# vstupyPCF8574.net
KiCad netlist of a schematic drawn in EAGLE
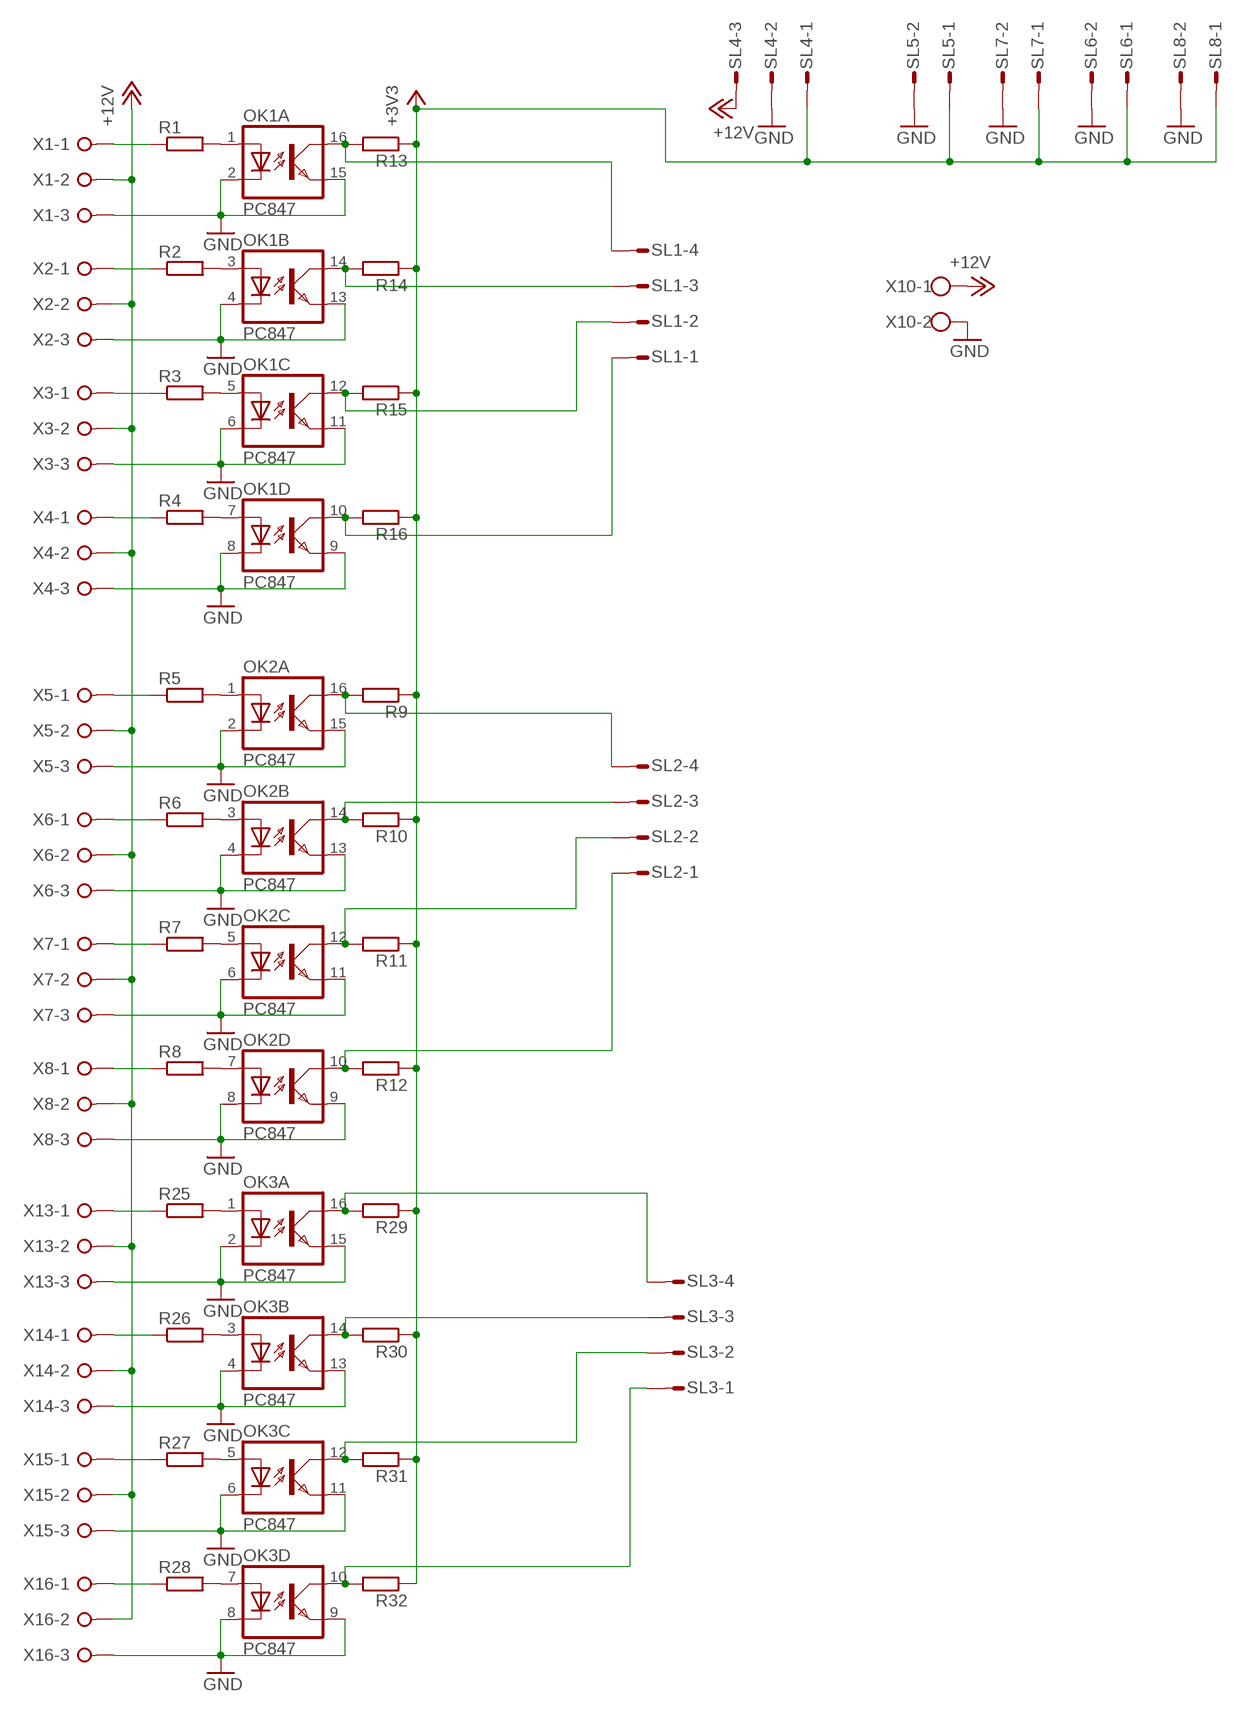
[diagram p0: schematic, sheet 1]

(export (version "E")
  (design (tool "Eeschema 10.0.6"))
  (components
    (comp (ref "OK1")
      (value "PC847")
      (footprint "eagle-import:DIL16")
      (libsource (lib "eagle-import") (part "PC847"))
    )
    (comp (ref "OK2")
      (value "PC847")
      (footprint "eagle-import:DIL16")
      (libsource (lib "eagle-import") (part "PC847"))
    )
    (comp (ref "OK3")
      (value "PC847")
      (footprint "eagle-import:DIL16")
      (libsource (lib "eagle-import") (part "PC847"))
    )
    (comp (ref "R1")
      (value "R-EU_0204/5")
      (footprint "eagle-import:0204_5")
      (libsource (lib "eagle-import") (part "R-EU_0204/5"))
    )
    (comp (ref "R2")
      (value "R-EU_0204/5")
      (footprint "eagle-import:0204_5")
      (libsource (lib "eagle-import") (part "R-EU_0204/5"))
    )
    (comp (ref "R3")
      (value "R-EU_0204/5")
      (footprint "eagle-import:0204_5")
      (libsource (lib "eagle-import") (part "R-EU_0204/5"))
    )
    (comp (ref "R4")
      (value "R-EU_0204/5")
      (footprint "eagle-import:0204_5")
      (libsource (lib "eagle-import") (part "R-EU_0204/5"))
    )
    (comp (ref "R5")
      (value "R-EU_0204/5")
      (footprint "eagle-import:0204_5")
      (libsource (lib "eagle-import") (part "R-EU_0204/5"))
    )
    (comp (ref "R6")
      (value "R-EU_0204/5")
      (footprint "eagle-import:0204_5")
      (libsource (lib "eagle-import") (part "R-EU_0204/5"))
    )
    (comp (ref "R7")
      (value "R-EU_0204/5")
      (footprint "eagle-import:0204_5")
      (libsource (lib "eagle-import") (part "R-EU_0204/5"))
    )
    (comp (ref "R8")
      (value "R-EU_0204/5")
      (footprint "eagle-import:0204_5")
      (libsource (lib "eagle-import") (part "R-EU_0204/5"))
    )
    (comp (ref "R9")
      (value "R-EU_0204/5")
      (footprint "eagle-import:0204_5")
      (libsource (lib "eagle-import") (part "R-EU_0204/5"))
    )
    (comp (ref "R10")
      (value "R-EU_0204/5")
      (footprint "eagle-import:0204_5")
      (libsource (lib "eagle-import") (part "R-EU_0204/5"))
    )
    (comp (ref "R11")
      (value "R-EU_0204/5")
      (footprint "eagle-import:0204_5")
      (libsource (lib "eagle-import") (part "R-EU_0204/5"))
    )
    (comp (ref "R12")
      (value "R-EU_0204/5")
      (footprint "eagle-import:0204_5")
      (libsource (lib "eagle-import") (part "R-EU_0204/5"))
    )
    (comp (ref "R13")
      (value "R-EU_0204/5")
      (footprint "eagle-import:0204_5")
      (libsource (lib "eagle-import") (part "R-EU_0204/5"))
    )
    (comp (ref "R14")
      (value "R-EU_0204/5")
      (footprint "eagle-import:0204_5")
      (libsource (lib "eagle-import") (part "R-EU_0204/5"))
    )
    (comp (ref "R15")
      (value "R-EU_0204/5")
      (footprint "eagle-import:0204_5")
      (libsource (lib "eagle-import") (part "R-EU_0204/5"))
    )
    (comp (ref "R16")
      (value "R-EU_0204/5")
      (footprint "eagle-import:0204_5")
      (libsource (lib "eagle-import") (part "R-EU_0204/5"))
    )
    (comp (ref "R25")
      (value "R-EU_0204/5")
      (footprint "eagle-import:0204_5")
      (libsource (lib "eagle-import") (part "R-EU_0204/5"))
    )
    (comp (ref "R26")
      (value "R-EU_0204/5")
      (footprint "eagle-import:0204_5")
      (libsource (lib "eagle-import") (part "R-EU_0204/5"))
    )
    (comp (ref "R27")
      (value "R-EU_0204/5")
      (footprint "eagle-import:0204_5")
      (libsource (lib "eagle-import") (part "R-EU_0204/5"))
    )
    (comp (ref "R28")
      (value "R-EU_0204/5")
      (footprint "eagle-import:0204_5")
      (libsource (lib "eagle-import") (part "R-EU_0204/5"))
    )
    (comp (ref "R29")
      (value "R-EU_0204/5")
      (footprint "eagle-import:0204_5")
      (libsource (lib "eagle-import") (part "R-EU_0204/5"))
    )
    (comp (ref "R30")
      (value "R-EU_0204/5")
      (footprint "eagle-import:0204_5")
      (libsource (lib "eagle-import") (part "R-EU_0204/5"))
    )
    (comp (ref "R31")
      (value "R-EU_0204/5")
      (footprint "eagle-import:0204_5")
      (libsource (lib "eagle-import") (part "R-EU_0204/5"))
    )
    (comp (ref "R32")
      (value "R-EU_0204/5")
      (footprint "eagle-import:0204_5")
      (libsource (lib "eagle-import") (part "R-EU_0204/5"))
    )
    (comp (ref "SL1")
      (value "M04S")
      (footprint "eagle-import:04P")
      (libsource (lib "eagle-import") (part "M04S"))
    )
    (comp (ref "SL2")
      (value "M04S")
      (footprint "eagle-import:04P")
      (libsource (lib "eagle-import") (part "M04S"))
    )
    (comp (ref "SL3")
      (value "M04S")
      (footprint "eagle-import:04P")
      (libsource (lib "eagle-import") (part "M04S"))
    )
    (comp (ref "SL4")
      (value "M03S")
      (footprint "eagle-import:03P")
      (libsource (lib "eagle-import") (part "M03S"))
    )
    (comp (ref "SL5")
      (value "M02S")
      (footprint "eagle-import:02P")
      (libsource (lib "eagle-import") (part "M02S"))
    )
    (comp (ref "SL6")
      (value "M02S")
      (footprint "eagle-import:02P")
      (libsource (lib "eagle-import") (part "M02S"))
    )
    (comp (ref "SL7")
      (value "M02S")
      (footprint "eagle-import:02P")
      (libsource (lib "eagle-import") (part "M02S"))
    )
    (comp (ref "SL8")
      (value "M02S")
      (footprint "eagle-import:02P")
      (libsource (lib "eagle-import") (part "M02S"))
    )
    (comp (ref "X1")
      (value "W237-3E")
      (footprint "eagle-import:W237-3E")
      (libsource (lib "eagle-import") (part "W237-3E"))
    )
    (comp (ref "X2")
      (value "W237-3E")
      (footprint "eagle-import:W237-3E")
      (libsource (lib "eagle-import") (part "W237-3E"))
    )
    (comp (ref "X3")
      (value "W237-3E")
      (footprint "eagle-import:W237-3E")
      (libsource (lib "eagle-import") (part "W237-3E"))
    )
    (comp (ref "X4")
      (value "W237-3E")
      (footprint "eagle-import:W237-3E")
      (libsource (lib "eagle-import") (part "W237-3E"))
    )
    (comp (ref "X5")
      (value "W237-3E")
      (footprint "eagle-import:W237-3E")
      (libsource (lib "eagle-import") (part "W237-3E"))
    )
    (comp (ref "X6")
      (value "W237-3E")
      (footprint "eagle-import:W237-3E")
      (libsource (lib "eagle-import") (part "W237-3E"))
    )
    (comp (ref "X7")
      (value "W237-3E")
      (footprint "eagle-import:W237-3E")
      (libsource (lib "eagle-import") (part "W237-3E"))
    )
    (comp (ref "X8")
      (value "W237-3E")
      (footprint "eagle-import:W237-3E")
      (libsource (lib "eagle-import") (part "W237-3E"))
    )
    (comp (ref "X10")
      (value "W237-102")
      (footprint "eagle-import:W237-102")
      (fields (field (name "MPN") "237-102"))
      (libsource (lib "eagle-import") (part "W237-102"))
    )
    (comp (ref "X13")
      (value "W237-3E")
      (footprint "eagle-import:W237-3E")
      (libsource (lib "eagle-import") (part "W237-3E"))
    )
    (comp (ref "X14")
      (value "W237-3E")
      (footprint "eagle-import:W237-3E")
      (libsource (lib "eagle-import") (part "W237-3E"))
    )
    (comp (ref "X15")
      (value "W237-3E")
      (footprint "eagle-import:W237-3E")
      (libsource (lib "eagle-import") (part "W237-3E"))
    )
    (comp (ref "X16")
      (value "W237-3E")
      (footprint "eagle-import:W237-3E")
      (libsource (lib "eagle-import") (part "W237-3E"))
    )
  )
  (nets
    (net (code "1") (name "+3V3") (class "Default")
      (node (ref "R10") (pin "1") (pinfunction "1_1") (pintype "passive"))
      (node (ref "R11") (pin "1") (pinfunction "1_1") (pintype "passive"))
      (node (ref "R12") (pin "1") (pinfunction "1_1") (pintype "passive"))
      (node (ref "R13") (pin "1") (pinfunction "1_1") (pintype "passive"))
      (node (ref "R14") (pin "1") (pinfunction "1_1") (pintype "passive"))
      (node (ref "R15") (pin "1") (pinfunction "1_1") (pintype "passive"))
      (node (ref "R16") (pin "1") (pinfunction "1_1") (pintype "passive"))
      (node (ref "R29") (pin "1") (pinfunction "1_1") (pintype "passive"))
      (node (ref "R30") (pin "1") (pinfunction "1_1") (pintype "passive"))
      (node (ref "R31") (pin "1") (pinfunction "1_1") (pintype "passive"))
      (node (ref "R32") (pin "1") (pinfunction "1_1") (pintype "passive"))
      (node (ref "R9") (pin "1") (pinfunction "1_1") (pintype "passive"))
      (node (ref "SL4") (pin "1") (pinfunction "S_1") (pintype "passive"))
      (node (ref "SL5") (pin "1") (pinfunction "S_1") (pintype "passive"))
      (node (ref "SL6") (pin "1") (pinfunction "S_1") (pintype "passive"))
      (node (ref "SL7") (pin "1") (pinfunction "S_1") (pintype "passive"))
      (node (ref "SL8") (pin "1") (pinfunction "S_1") (pintype "passive"))
    )
    (net (code "2") (name "+12V") (class "Default")
      (node (ref "SL4") (pin "3") (pinfunction "S_3") (pintype "passive"))
      (node (ref "X1") (pin "2") (pinfunction "KL_2") (pintype "passive"))
      (node (ref "X10") (pin "1") (pinfunction "KL_1") (pintype "passive"))
      (node (ref "X13") (pin "2") (pinfunction "KL_2") (pintype "passive"))
      (node (ref "X14") (pin "2") (pinfunction "KL_2") (pintype "passive"))
      (node (ref "X15") (pin "2") (pinfunction "KL_2") (pintype "passive"))
      (node (ref "X16") (pin "2") (pinfunction "KL_2") (pintype "passive"))
      (node (ref "X2") (pin "2") (pinfunction "KL_2") (pintype "passive"))
      (node (ref "X3") (pin "2") (pinfunction "KL_2") (pintype "passive"))
      (node (ref "X4") (pin "2") (pinfunction "KL_2") (pintype "passive"))
      (node (ref "X5") (pin "2") (pinfunction "KL_2") (pintype "passive"))
      (node (ref "X6") (pin "2") (pinfunction "KL_2") (pintype "passive"))
      (node (ref "X7") (pin "2") (pinfunction "KL_2") (pintype "passive"))
      (node (ref "X8") (pin "2") (pinfunction "KL_2") (pintype "passive"))
    )
    (net (code "3") (name "GND") (class "Default")
      (node (ref "OK1") (pin "11") (pinfunction "EMIT_11") (pintype "passive"))
      (node (ref "OK1") (pin "13") (pinfunction "EMIT_13") (pintype "passive"))
      (node (ref "OK1") (pin "15") (pinfunction "EMIT_15") (pintype "passive"))
      (node (ref "OK1") (pin "2") (pinfunction "C_2") (pintype "passive"))
      (node (ref "OK1") (pin "4") (pinfunction "C_4") (pintype "passive"))
      (node (ref "OK1") (pin "6") (pinfunction "C_6") (pintype "passive"))
      (node (ref "OK1") (pin "8") (pinfunction "C_8") (pintype "passive"))
      (node (ref "OK1") (pin "9") (pinfunction "EMIT_9") (pintype "passive"))
      (node (ref "OK2") (pin "11") (pinfunction "EMIT_11") (pintype "passive"))
      (node (ref "OK2") (pin "13") (pinfunction "EMIT_13") (pintype "passive"))
      (node (ref "OK2") (pin "15") (pinfunction "EMIT_15") (pintype "passive"))
      (node (ref "OK2") (pin "2") (pinfunction "C_2") (pintype "passive"))
      (node (ref "OK2") (pin "4") (pinfunction "C_4") (pintype "passive"))
      (node (ref "OK2") (pin "6") (pinfunction "C_6") (pintype "passive"))
      (node (ref "OK2") (pin "8") (pinfunction "C_8") (pintype "passive"))
      (node (ref "OK2") (pin "9") (pinfunction "EMIT_9") (pintype "passive"))
      (node (ref "OK3") (pin "11") (pinfunction "EMIT_11") (pintype "passive"))
      (node (ref "OK3") (pin "13") (pinfunction "EMIT_13") (pintype "passive"))
      (node (ref "OK3") (pin "15") (pinfunction "EMIT_15") (pintype "passive"))
      (node (ref "OK3") (pin "2") (pinfunction "C_2") (pintype "passive"))
      (node (ref "OK3") (pin "4") (pinfunction "C_4") (pintype "passive"))
      (node (ref "OK3") (pin "6") (pinfunction "C_6") (pintype "passive"))
      (node (ref "OK3") (pin "8") (pinfunction "C_8") (pintype "passive"))
      (node (ref "OK3") (pin "9") (pinfunction "EMIT_9") (pintype "passive"))
      (node (ref "SL4") (pin "2") (pinfunction "S_2") (pintype "passive"))
      (node (ref "SL5") (pin "2") (pinfunction "S_2") (pintype "passive"))
      (node (ref "SL6") (pin "2") (pinfunction "S_2") (pintype "passive"))
      (node (ref "SL7") (pin "2") (pinfunction "S_2") (pintype "passive"))
      (node (ref "SL8") (pin "2") (pinfunction "S_2") (pintype "passive"))
      (node (ref "X1") (pin "3") (pinfunction "KL_3") (pintype "passive"))
      (node (ref "X10") (pin "2") (pinfunction "KL_2") (pintype "passive"))
      (node (ref "X13") (pin "3") (pinfunction "KL_3") (pintype "passive"))
      (node (ref "X14") (pin "3") (pinfunction "KL_3") (pintype "passive"))
      (node (ref "X15") (pin "3") (pinfunction "KL_3") (pintype "passive"))
      (node (ref "X16") (pin "3") (pinfunction "KL_3") (pintype "passive"))
      (node (ref "X2") (pin "3") (pinfunction "KL_3") (pintype "passive"))
      (node (ref "X3") (pin "3") (pinfunction "KL_3") (pintype "passive"))
      (node (ref "X4") (pin "3") (pinfunction "KL_3") (pintype "passive"))
      (node (ref "X5") (pin "3") (pinfunction "KL_3") (pintype "passive"))
      (node (ref "X6") (pin "3") (pinfunction "KL_3") (pintype "passive"))
      (node (ref "X7") (pin "3") (pinfunction "KL_3") (pintype "passive"))
      (node (ref "X8") (pin "3") (pinfunction "KL_3") (pintype "passive"))
    )
    (net (code "4") (name "Net-(OK1A-A)") (class "Default")
      (node (ref "OK1") (pin "1") (pinfunction "A_1") (pintype "passive"))
      (node (ref "R1") (pin "2") (pinfunction "2_2") (pintype "passive"))
    )
    (net (code "5") (name "Net-(OK1A-COL)") (class "Default")
      (node (ref "OK1") (pin "16") (pinfunction "COL_16") (pintype "passive"))
      (node (ref "R13") (pin "2") (pinfunction "2_2") (pintype "passive"))
      (node (ref "SL1") (pin "4") (pinfunction "S_4") (pintype "passive"))
    )
    (net (code "6") (name "Net-(OK1B-A)") (class "Default")
      (node (ref "OK1") (pin "3") (pinfunction "A_3") (pintype "passive"))
      (node (ref "R2") (pin "2") (pinfunction "2_2") (pintype "passive"))
    )
    (net (code "7") (name "Net-(OK1B-COL)") (class "Default")
      (node (ref "OK1") (pin "14") (pinfunction "COL_14") (pintype "passive"))
      (node (ref "R14") (pin "2") (pinfunction "2_2") (pintype "passive"))
      (node (ref "SL1") (pin "3") (pinfunction "S_3") (pintype "passive"))
    )
    (net (code "8") (name "Net-(OK1C-A)") (class "Default")
      (node (ref "OK1") (pin "5") (pinfunction "A_5") (pintype "passive"))
      (node (ref "R3") (pin "2") (pinfunction "2_2") (pintype "passive"))
    )
    (net (code "9") (name "Net-(OK1C-COL)") (class "Default")
      (node (ref "OK1") (pin "12") (pinfunction "COL_12") (pintype "passive"))
      (node (ref "R15") (pin "2") (pinfunction "2_2") (pintype "passive"))
      (node (ref "SL1") (pin "2") (pinfunction "S_2") (pintype "passive"))
    )
    (net (code "10") (name "Net-(OK1D-A)") (class "Default")
      (node (ref "OK1") (pin "7") (pinfunction "A_7") (pintype "passive"))
      (node (ref "R4") (pin "2") (pinfunction "2_2") (pintype "passive"))
    )
    (net (code "11") (name "Net-(OK1D-COL)") (class "Default")
      (node (ref "OK1") (pin "10") (pinfunction "COL_10") (pintype "passive"))
      (node (ref "R16") (pin "2") (pinfunction "2_2") (pintype "passive"))
      (node (ref "SL1") (pin "1") (pinfunction "S_1") (pintype "passive"))
    )
    (net (code "12") (name "Net-(OK2A-A)") (class "Default")
      (node (ref "OK2") (pin "1") (pinfunction "A_1") (pintype "passive"))
      (node (ref "R5") (pin "2") (pinfunction "2_2") (pintype "passive"))
    )
    (net (code "13") (name "Net-(OK2A-COL)") (class "Default")
      (node (ref "OK2") (pin "16") (pinfunction "COL_16") (pintype "passive"))
      (node (ref "R9") (pin "2") (pinfunction "2_2") (pintype "passive"))
      (node (ref "SL2") (pin "4") (pinfunction "S_4") (pintype "passive"))
    )
    (net (code "14") (name "Net-(OK2B-A)") (class "Default")
      (node (ref "OK2") (pin "3") (pinfunction "A_3") (pintype "passive"))
      (node (ref "R6") (pin "2") (pinfunction "2_2") (pintype "passive"))
    )
    (net (code "15") (name "Net-(OK2B-COL)") (class "Default")
      (node (ref "OK2") (pin "14") (pinfunction "COL_14") (pintype "passive"))
      (node (ref "R10") (pin "2") (pinfunction "2_2") (pintype "passive"))
      (node (ref "SL2") (pin "3") (pinfunction "S_3") (pintype "passive"))
    )
    (net (code "16") (name "Net-(OK2C-A)") (class "Default")
      (node (ref "OK2") (pin "5") (pinfunction "A_5") (pintype "passive"))
      (node (ref "R7") (pin "2") (pinfunction "2_2") (pintype "passive"))
    )
    (net (code "17") (name "Net-(OK2C-COL)") (class "Default")
      (node (ref "OK2") (pin "12") (pinfunction "COL_12") (pintype "passive"))
      (node (ref "R11") (pin "2") (pinfunction "2_2") (pintype "passive"))
      (node (ref "SL2") (pin "2") (pinfunction "S_2") (pintype "passive"))
    )
    (net (code "18") (name "Net-(OK2D-A)") (class "Default")
      (node (ref "OK2") (pin "7") (pinfunction "A_7") (pintype "passive"))
      (node (ref "R8") (pin "2") (pinfunction "2_2") (pintype "passive"))
    )
    (net (code "19") (name "Net-(OK2D-COL)") (class "Default")
      (node (ref "OK2") (pin "10") (pinfunction "COL_10") (pintype "passive"))
      (node (ref "R12") (pin "2") (pinfunction "2_2") (pintype "passive"))
      (node (ref "SL2") (pin "1") (pinfunction "S_1") (pintype "passive"))
    )
    (net (code "20") (name "Net-(OK3A-A)") (class "Default")
      (node (ref "OK3") (pin "1") (pinfunction "A_1") (pintype "passive"))
      (node (ref "R25") (pin "2") (pinfunction "2_2") (pintype "passive"))
    )
    (net (code "21") (name "Net-(OK3A-COL)") (class "Default")
      (node (ref "OK3") (pin "16") (pinfunction "COL_16") (pintype "passive"))
      (node (ref "R29") (pin "2") (pinfunction "2_2") (pintype "passive"))
      (node (ref "SL3") (pin "4") (pinfunction "S_4") (pintype "passive"))
    )
    (net (code "22") (name "Net-(OK3B-A)") (class "Default")
      (node (ref "OK3") (pin "3") (pinfunction "A_3") (pintype "passive"))
      (node (ref "R26") (pin "2") (pinfunction "2_2") (pintype "passive"))
    )
    (net (code "23") (name "Net-(OK3B-COL)") (class "Default")
      (node (ref "OK3") (pin "14") (pinfunction "COL_14") (pintype "passive"))
      (node (ref "R30") (pin "2") (pinfunction "2_2") (pintype "passive"))
      (node (ref "SL3") (pin "3") (pinfunction "S_3") (pintype "passive"))
    )
    (net (code "24") (name "Net-(OK3C-A)") (class "Default")
      (node (ref "OK3") (pin "5") (pinfunction "A_5") (pintype "passive"))
      (node (ref "R27") (pin "2") (pinfunction "2_2") (pintype "passive"))
    )
    (net (code "25") (name "Net-(OK3C-COL)") (class "Default")
      (node (ref "OK3") (pin "12") (pinfunction "COL_12") (pintype "passive"))
      (node (ref "R31") (pin "2") (pinfunction "2_2") (pintype "passive"))
      (node (ref "SL3") (pin "2") (pinfunction "S_2") (pintype "passive"))
    )
    (net (code "26") (name "Net-(OK3D-A)") (class "Default")
      (node (ref "OK3") (pin "7") (pinfunction "A_7") (pintype "passive"))
      (node (ref "R28") (pin "2") (pinfunction "2_2") (pintype "passive"))
    )
    (net (code "27") (name "Net-(OK3D-COL)") (class "Default")
      (node (ref "OK3") (pin "10") (pinfunction "COL_10") (pintype "passive"))
      (node (ref "R32") (pin "2") (pinfunction "2_2") (pintype "passive"))
      (node (ref "SL3") (pin "1") (pinfunction "S_1") (pintype "passive"))
    )
    (net (code "28") (name "Net-(X1A-KL)") (class "Default")
      (node (ref "R1") (pin "1") (pinfunction "1_1") (pintype "passive"))
      (node (ref "X1") (pin "1") (pinfunction "KL_1") (pintype "passive"))
    )
    (net (code "29") (name "Net-(X2A-KL)") (class "Default")
      (node (ref "R2") (pin "1") (pinfunction "1_1") (pintype "passive"))
      (node (ref "X2") (pin "1") (pinfunction "KL_1") (pintype "passive"))
    )
    (net (code "30") (name "Net-(X3A-KL)") (class "Default")
      (node (ref "R3") (pin "1") (pinfunction "1_1") (pintype "passive"))
      (node (ref "X3") (pin "1") (pinfunction "KL_1") (pintype "passive"))
    )
    (net (code "31") (name "Net-(X4A-KL)") (class "Default")
      (node (ref "R4") (pin "1") (pinfunction "1_1") (pintype "passive"))
      (node (ref "X4") (pin "1") (pinfunction "KL_1") (pintype "passive"))
    )
    (net (code "32") (name "Net-(X5A-KL)") (class "Default")
      (node (ref "R5") (pin "1") (pinfunction "1_1") (pintype "passive"))
      (node (ref "X5") (pin "1") (pinfunction "KL_1") (pintype "passive"))
    )
    (net (code "33") (name "Net-(X6A-KL)") (class "Default")
      (node (ref "R6") (pin "1") (pinfunction "1_1") (pintype "passive"))
      (node (ref "X6") (pin "1") (pinfunction "KL_1") (pintype "passive"))
    )
    (net (code "34") (name "Net-(X7A-KL)") (class "Default")
      (node (ref "R7") (pin "1") (pinfunction "1_1") (pintype "passive"))
      (node (ref "X7") (pin "1") (pinfunction "KL_1") (pintype "passive"))
    )
    (net (code "35") (name "Net-(X8A-KL)") (class "Default")
      (node (ref "R8") (pin "1") (pinfunction "1_1") (pintype "passive"))
      (node (ref "X8") (pin "1") (pinfunction "KL_1") (pintype "passive"))
    )
    (net (code "36") (name "Net-(X13A-KL)") (class "Default")
      (node (ref "R25") (pin "1") (pinfunction "1_1") (pintype "passive"))
      (node (ref "X13") (pin "1") (pinfunction "KL_1") (pintype "passive"))
    )
    (net (code "37") (name "Net-(X14A-KL)") (class "Default")
      (node (ref "R26") (pin "1") (pinfunction "1_1") (pintype "passive"))
      (node (ref "X14") (pin "1") (pinfunction "KL_1") (pintype "passive"))
    )
    (net (code "38") (name "Net-(X15A-KL)") (class "Default")
      (node (ref "R27") (pin "1") (pinfunction "1_1") (pintype "passive"))
      (node (ref "X15") (pin "1") (pinfunction "KL_1") (pintype "passive"))
    )
    (net (code "39") (name "Net-(X16A-KL)") (class "Default")
      (node (ref "R28") (pin "1") (pinfunction "1_1") (pintype "passive"))
      (node (ref "X16") (pin "1") (pinfunction "KL_1") (pintype "passive"))
    )
  )
)
